# projet_pcb_nucleo_g431.net
KiCad netlist of a schematic drawn in Altium Designer
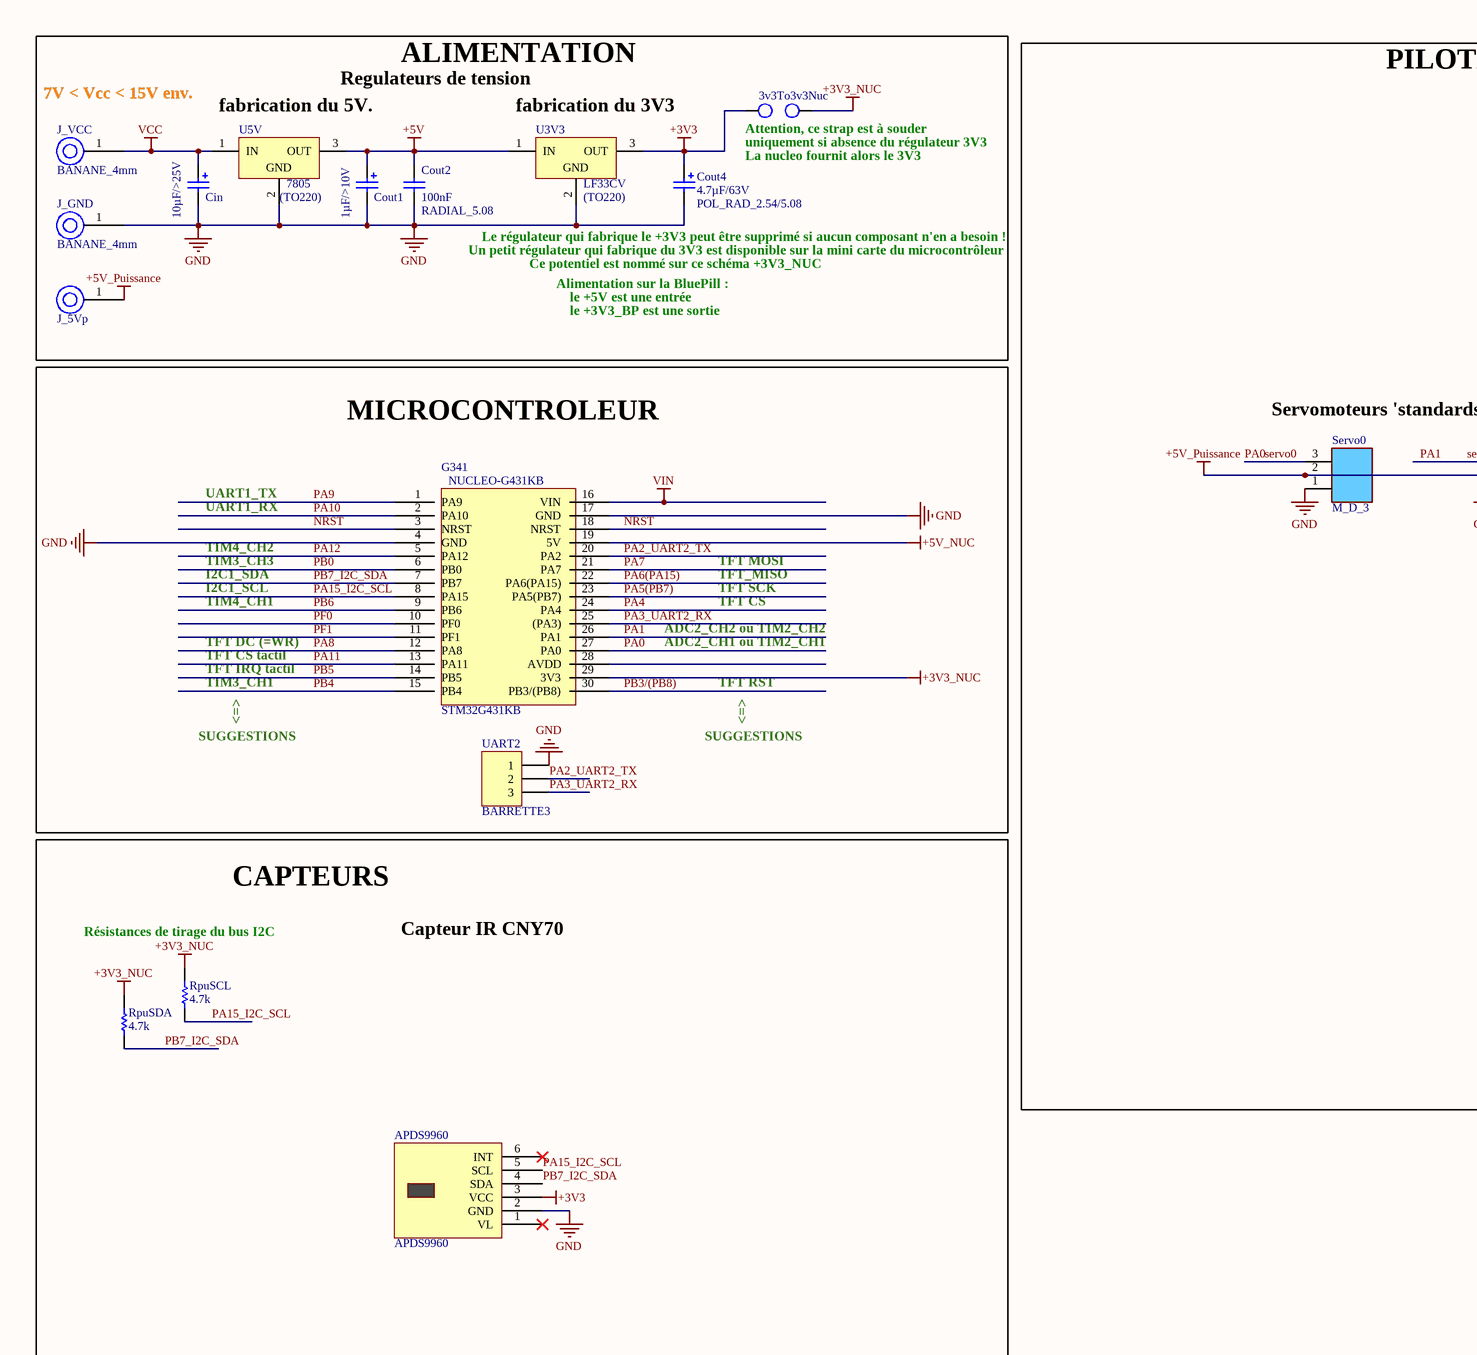
[diagram p0: projet_pcb_nucleo_g431.SchDoc, left]
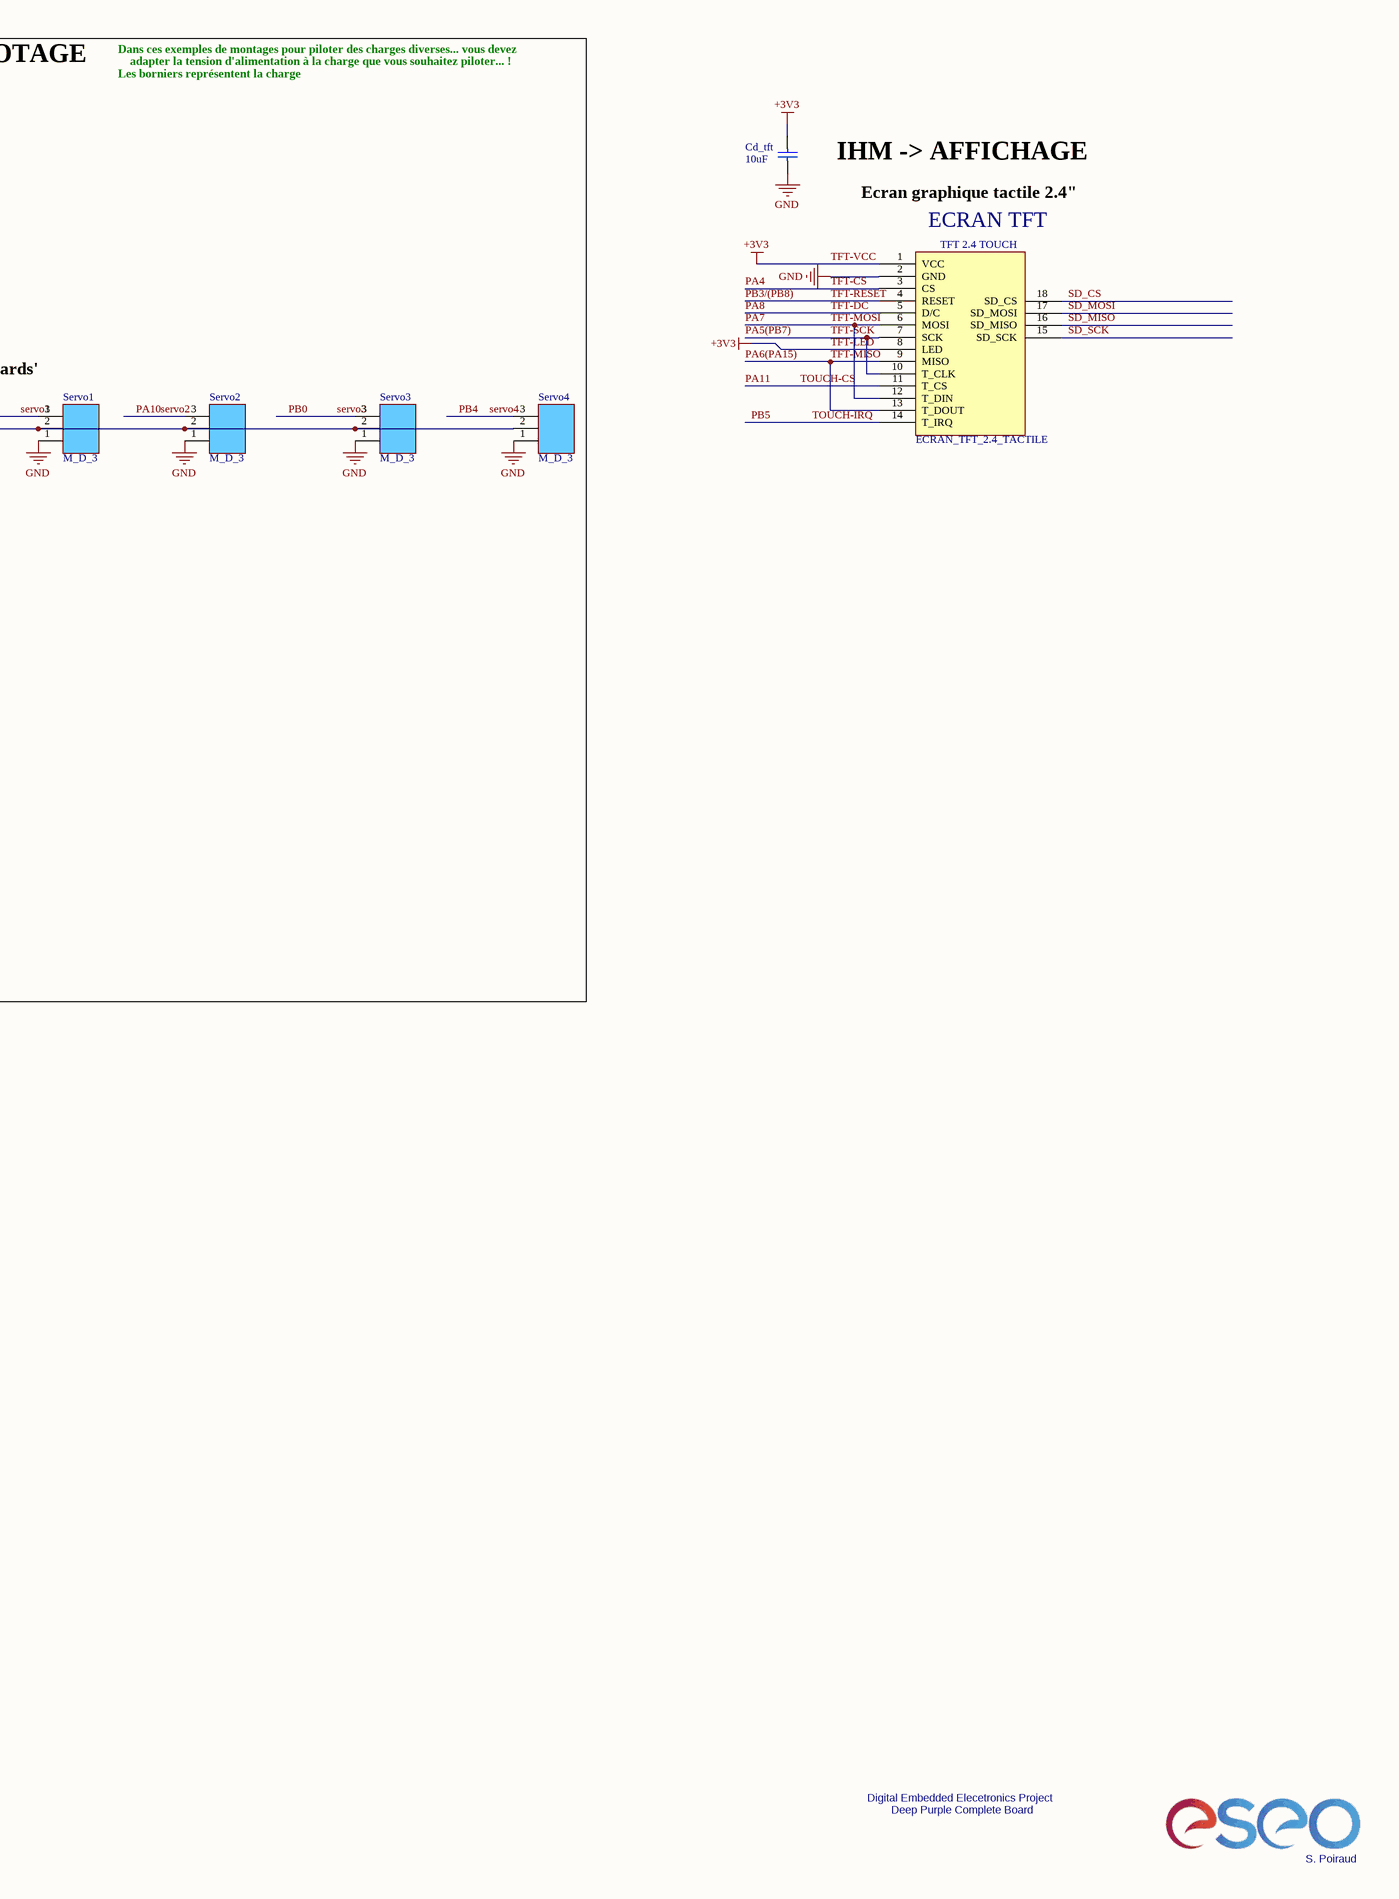
[diagram p1: projet_pcb_nucleo_g431.SchDoc, right]

(export (version "E")
  (design (tool "Eeschema 10.0.6"))
  (components
    (comp (ref "3v3To3v3Nuc")
      (value "JUMPER2")
      (footprint "BARRETTE_2_M_D")
      (description "BARRETTE 2 CONTACTS 1 RANGEE MALE DROITE")
      (libsource (lib "connecteurs") (part "JUMPER2"))
    )
    (comp (ref "APDS9960")
      (value "APDS9960")
      (footprint "APDS9960")
      (libsource (lib "DEEP") (part "APDS9960"))
    )
    (comp (ref "Cd_tft")
      (value "10uF")
      (footprint "C0805_N")
      (description "CONDENSATEUR CMS CERAMIQUE 0805")
      (libsource (lib "composants passifs") (part "CONDENSATEUR_CMS_CER_0805"))
    )
    (comp (ref "Cin")
      (value "10µF/>25V")
      (footprint "CONDENSATEUR_POLARISE_ELECTROLYTIQUE_RADIAL_2.0/5.08")
      (description "CONDENSATEUR POLARISE ELECTROLYTIQUE RADIAL 2.0/5.08")
      (fields (field (name "Comment") "CONDENSATEUR_POL_ELECTROLY_RAD_2.0/5.08"))
      (libsource (lib "composants passifs") (part "CONDENSATEUR_POL_ELECTROLY_RAD_2.0/5.08"))
    )
    (comp (ref "Cout1")
      (value "1µF/>10V")
      (footprint "CONDENSATEUR_POLARISE_ELECTROLYTIQUE_RADIAL_2.0/5.08")
      (description "CONDENSATEUR POLARISE ELECTROLYTIQUE RADIAL 2.0/5.08")
      (fields (field (name "Comment") "CONDENSATEUR_POL_ELECTROLY_RAD_2.0/5.08"))
      (libsource (lib "composants passifs") (part "CONDENSATEUR_POL_ELECTROLY_RAD_2.0/5.08"))
    )
    (comp (ref "Cout2")
      (value "100nF")
      (footprint "CONDENSATEUR_CERAMIQUE_RADIAL_5.08")
      (description "CONDENSATEUR TRAVERSANT CERAMIQUE RADIAL 5.08mm")
      (fields (field (name "TYPE") "RADIAL_5.08") (field (name "Comment") "CONDENSATEUR_CER_RAD_5.08"))
      (libsource (lib "composants passifs") (part "CONDENSATEUR_CER_RAD_5.08"))
    )
    (comp (ref "Cout4")
      (value "4.7µF/63V")
      (footprint "CONDENSATEUR_POLARISE_ELECTROLYTIQUE_RADIAL_2.54/5.08")
      (description "CONDENSATEUR POLARISE ELECTROLYTIQUE RADIAL 2.54/5.08")
      (fields
        (field (name "TYPE") "POL_RAD_2.54/5.08")
        (field (name "Comment") "CONDENSATEUR_POL_ELECTROLY_RAD_2.54/5.08")
      )
      (libsource (lib "composants passifs") (part "CONDENSATEUR_POL_ELECTROLY_RAD_2.54/5.08"))
    )
    (comp (ref "G341")
      (value "STM32G431KB")
      (footprint "NUCLEO-G431KB")
      (libsource (lib "circuits integres") (part "G431_Nucleo"))
    )
    (comp (ref "J_5Vp")
      (value "DOUILLE BANANE 4mm")
      (footprint "DOUILLE_BANANE_4mm")
      (description "DOUILLE BANANE 4 mm")
      (libsource (lib "connecteurs") (part "DOUILLE_BANANE_4mm"))
    )
    (comp (ref "J_GND")
      (value "DOUILLE BANANE 4mm")
      (footprint "DOUILLE_BANANE_4mm")
      (description "DOUILLE BANANE 4 mm")
      (fields (field (name "TYPE") "BANANE_4mm"))
      (libsource (lib "connecteurs") (part "DOUILLE_BANANE_4mm"))
    )
    (comp (ref "J_VCC")
      (value "DOUILLE BANANE 4mm")
      (footprint "DOUILLE_BANANE_4mm")
      (description "DOUILLE BANANE 4 mm")
      (fields (field (name "TYPE") "BANANE_4mm"))
      (libsource (lib "connecteurs") (part "DOUILLE_BANANE_4mm"))
    )
    (comp (ref "RpuSCL")
      (value "4.7k")
      (footprint "R1206_N")
      (description "RESISTANCE CMS 1206")
      (fields (field (name "Comment") "RESISTANCE_CMS_1206"))
      (libsource (lib "composants passifs") (part "RESISTANCE_CMS_1206"))
    )
    (comp (ref "RpuSDA")
      (value "4.7k")
      (footprint "R1206_N")
      (description "RESISTANCE CMS 1206")
      (fields (field (name "Comment") "RESISTANCE_CMS_1206"))
      (libsource (lib "composants passifs") (part "RESISTANCE_CMS_1206"))
    )
    (comp (ref "Servo0")
      (value "BARRETTE 3 CONTACTS 1 RANGEE MALE DROITE")
      (footprint "BARRETTE_3_M_D")
      (fields (field (name "TYPE") "M_D_3"))
      (libsource (lib "connecteurs") (part "BARRETTE_3 CONTACTS_1 RANGEE_MALE_DROITE"))
    )
    (comp (ref "Servo1")
      (value "BARRETTE 3 CONTACTS 1 RANGEE MALE DROITE")
      (footprint "BARRETTE_3_M_D")
      (fields (field (name "TYPE") "M_D_3"))
      (libsource (lib "connecteurs") (part "BARRETTE_3 CONTACTS_1 RANGEE_MALE_DROITE"))
    )
    (comp (ref "Servo2")
      (value "BARRETTE 3 CONTACTS 1 RANGEE MALE DROITE")
      (footprint "BARRETTE_3_M_D")
      (fields (field (name "TYPE") "M_D_3"))
      (libsource (lib "connecteurs") (part "BARRETTE_3 CONTACTS_1 RANGEE_MALE_DROITE"))
    )
    (comp (ref "Servo3")
      (value "BARRETTE 3 CONTACTS 1 RANGEE MALE DROITE")
      (footprint "BARRETTE_3_M_D")
      (fields (field (name "TYPE") "M_D_3"))
      (libsource (lib "connecteurs") (part "BARRETTE_3 CONTACTS_1 RANGEE_MALE_DROITE"))
    )
    (comp (ref "Servo4")
      (value "BARRETTE 3 CONTACTS 1 RANGEE MALE DROITE")
      (footprint "BARRETTE_3_M_D")
      (fields (field (name "TYPE") "M_D_3"))
      (libsource (lib "connecteurs") (part "BARRETTE_3 CONTACTS_1 RANGEE_MALE_DROITE"))
    )
    (comp (ref "TFT1")
      (value "ECRAN_TFT_2.4_TACTILE")
      (footprint "ECRAN_TFT_2.4_TACTILE")
      (libsource (lib "affichage") (part "ECRAN_TFT_2.4_TACTILE"))
    )
    (comp (ref "U3V3")
      (value "REGULATEUR_TO220_78XX")
      (footprint "REGULATEUR_TO220_78XX")
      (description "REGULATEUR DE TENSION POSITIVE 78XX BOITIER TO220")
      (fields (field (name "TYPE") "LF33CV") (field (name "PACKAGE") "(TO220)"))
      (libsource (lib "composants actifs") (part "REGULATEUR_TO220_78XX"))
    )
    (comp (ref "U5V")
      (value "REGULATEUR_TO220_78XX")
      (footprint "REGULATEUR_TO220_78XX")
      (description "REGULATEUR DE TENSION POSITIVE 78XX BOITIER TO220")
      (fields (field (name "TYPE") "7805") (field (name "PACKAGE") "(TO220)"))
      (libsource (lib "composants actifs") (part "REGULATEUR_TO220_78XX"))
    )
    (comp (ref "UART2")
      (value "BARRETTE3")
      (footprint "HDR1X3")
      (description "Header, 3-Pin")
      (fields (field (name "PUBLISHER") "Altium Limited"))
      (libsource (lib "Connecteur") (part "BARRETTE3"))
    )
  )
  (nets
    (net (code "1") (name "+3V3") (class "Default")
      (node (ref "3v3To3v3Nuc") (pin "1") (pinfunction "1_1") (pintype "passive"))
      (node (ref "APDS9960") (pin "3") (pinfunction "VCC_3") (pintype "passive"))
      (node (ref "Cd_tft") (pin "2") (pinfunction "2_2") (pintype "passive"))
      (node (ref "Cout4") (pin "1") (pinfunction "1_1") (pintype "passive"))
      (node (ref "TFT1") (pin "1") (pinfunction "VCC_1") (pintype "passive"))
      (node (ref "TFT1") (pin "8") (pinfunction "LED_8") (pintype "passive"))
      (node (ref "U3V3") (pin "3") (pinfunction "OUT_3") (pintype "power_in"))
    )
    (net (code "2") (name "+3V3_NUC") (class "Default")
      (node (ref "3v3To3v3Nuc") (pin "2") (pinfunction "2_2") (pintype "passive"))
      (node (ref "G341") (pin "29") (pinfunction "3V3_29") (pintype "passive"))
      (node (ref "RpuSCL") (pin "2") (pinfunction "2_2") (pintype "passive"))
      (node (ref "RpuSDA") (pin "2") (pinfunction "2_2") (pintype "passive"))
    )
    (net (code "3") (name "+5V") (class "Default")
      (node (ref "Cout1") (pin "1") (pinfunction "1_1") (pintype "passive"))
      (node (ref "Cout2") (pin "2") (pinfunction "2_2") (pintype "passive"))
      (node (ref "U3V3") (pin "1") (pinfunction "IN_1") (pintype "power_in"))
      (node (ref "U5V") (pin "3") (pinfunction "OUT_3") (pintype "power_in"))
    )
    (net (code "4") (name "+5V_NUC") (class "Default")
      (node (ref "G341") (pin "19") (pinfunction "5V_19") (pintype "power_in"))
    )
    (net (code "5") (name "+5V_Puissance") (class "Default")
      (node (ref "J_5Vp") (pin "1") (pinfunction "1_1") (pintype "passive"))
      (node (ref "Servo0") (pin "2") (pinfunction "2_2") (pintype "passive"))
      (node (ref "Servo1") (pin "2") (pinfunction "2_2") (pintype "passive"))
      (node (ref "Servo2") (pin "2") (pinfunction "2_2") (pintype "passive"))
      (node (ref "Servo3") (pin "2") (pinfunction "2_2") (pintype "passive"))
      (node (ref "Servo4") (pin "2") (pinfunction "2_2") (pintype "passive"))
    )
    (net (code "6") (name "/NRST") (class "Default")
      (node (ref "G341") (pin "18") (pinfunction "NRST_18") (pintype "passive"))
      (node (ref "G341") (pin "3") (pinfunction "NRST_3") (pintype "passive"))
    )
    (net (code "7") (name "/PA0") (class "Default")
      (node (ref "G341") (pin "27") (pinfunction "PA0_27") (pintype "passive"))
      (node (ref "Servo0") (pin "3") (pinfunction "3_3") (pintype "passive"))
    )
    (net (code "8") (name "/PA1") (class "Default")
      (node (ref "G341") (pin "26") (pinfunction "PA1_26") (pintype "passive"))
      (node (ref "Servo1") (pin "3") (pinfunction "3_3") (pintype "passive"))
    )
    (net (code "9") (name "/PA2_UART2_TX") (class "Default")
      (node (ref "G341") (pin "20") (pinfunction "PA2_20") (pintype "passive"))
      (node (ref "UART2") (pin "2") (pinfunction "2_2") (pintype "passive"))
    )
    (net (code "10") (name "/PA3_UART2_RX") (class "Default")
      (node (ref "G341") (pin "25") (pinfunction "(PA3)_25") (pintype "passive"))
      (node (ref "UART2") (pin "3") (pinfunction "3_3") (pintype "passive"))
    )
    (net (code "11") (name "/PA4") (class "Default")
      (node (ref "G341") (pin "24") (pinfunction "PA4_24") (pintype "passive"))
      (node (ref "TFT1") (pin "3") (pinfunction "CS_3") (pintype "passive"))
    )
    (net (code "12") (name "/PA5(PB7)") (class "Default")
      (node (ref "G341") (pin "23") (pinfunction "PA5(PB7)_23") (pintype "passive"))
      (node (ref "TFT1") (pin "10") (pinfunction "T_CLK_10") (pintype "passive"))
      (node (ref "TFT1") (pin "7") (pinfunction "SCK_7") (pintype "passive"))
    )
    (net (code "13") (name "/PA6(PA15)") (class "Default")
      (node (ref "G341") (pin "22") (pinfunction "PA6(PA15)_22") (pintype "passive"))
      (node (ref "TFT1") (pin "13") (pinfunction "T_DOUT_13") (pintype "passive"))
      (node (ref "TFT1") (pin "9") (pinfunction "MISO_9") (pintype "passive"))
    )
    (net (code "14") (name "/PA7") (class "Default")
      (node (ref "G341") (pin "21") (pinfunction "PA7_21") (pintype "passive"))
      (node (ref "TFT1") (pin "12") (pinfunction "T_DIN_12") (pintype "passive"))
      (node (ref "TFT1") (pin "6") (pinfunction "MOSI_6") (pintype "passive"))
    )
    (net (code "15") (name "/PA8") (class "Default")
      (node (ref "G341") (pin "12") (pinfunction "PA8_12") (pintype "passive"))
      (node (ref "TFT1") (pin "5") (pinfunction "D/C_5") (pintype "passive"))
    )
    (net (code "16") (name "/PA9") (class "Default")
      (node (ref "G341") (pin "1") (pinfunction "PA9_1") (pintype "passive"))
    )
    (net (code "17") (name "/PA10") (class "Default")
      (node (ref "G341") (pin "2") (pinfunction "PA10_2") (pintype "passive"))
      (node (ref "Servo2") (pin "3") (pinfunction "3_3") (pintype "passive"))
    )
    (net (code "18") (name "/PA11") (class "Default")
      (node (ref "G341") (pin "13") (pinfunction "PA11_13") (pintype "passive"))
      (node (ref "TFT1") (pin "11") (pinfunction "T_CS_11") (pintype "passive"))
    )
    (net (code "19") (name "/PA12") (class "Default")
      (node (ref "G341") (pin "5") (pinfunction "PA12_5") (pintype "passive"))
    )
    (net (code "20") (name "/PA15_I2C_SCL") (class "Default")
      (node (ref "APDS9960") (pin "5") (pinfunction "SCL_5") (pintype "passive"))
      (node (ref "G341") (pin "8") (pinfunction "PA15_8") (pintype "passive"))
      (node (ref "RpuSCL") (pin "1") (pinfunction "1_1") (pintype "passive"))
    )
    (net (code "21") (name "/PB0") (class "Default")
      (node (ref "G341") (pin "6") (pinfunction "PB0_6") (pintype "passive"))
      (node (ref "Servo3") (pin "3") (pinfunction "3_3") (pintype "passive"))
    )
    (net (code "22") (name "/PB3{slash}(PB8)") (class "Default")
      (node (ref "G341") (pin "30") (pinfunction "PB3/(PB8)_30") (pintype "passive"))
      (node (ref "TFT1") (pin "4") (pinfunction "RESET_4") (pintype "passive"))
    )
    (net (code "23") (name "/PB4") (class "Default")
      (node (ref "G341") (pin "15") (pinfunction "PB4_15") (pintype "passive"))
      (node (ref "Servo4") (pin "3") (pinfunction "3_3") (pintype "passive"))
    )
    (net (code "24") (name "/PB5") (class "Default")
      (node (ref "G341") (pin "14") (pinfunction "PB5_14") (pintype "passive"))
      (node (ref "TFT1") (pin "14") (pinfunction "T_IRQ_14") (pintype "passive"))
    )
    (net (code "25") (name "/PB6") (class "Default")
      (node (ref "G341") (pin "9") (pinfunction "PB6_9") (pintype "passive"))
    )
    (net (code "26") (name "/PB7_I2C_SDA") (class "Default")
      (node (ref "APDS9960") (pin "4") (pinfunction "SDA_4") (pintype "passive"))
      (node (ref "G341") (pin "7") (pinfunction "PB7_7") (pintype "passive"))
      (node (ref "RpuSDA") (pin "1") (pinfunction "1_1") (pintype "passive"))
    )
    (net (code "27") (name "/PF0") (class "Default")
      (node (ref "G341") (pin "10") (pinfunction "PF0_10") (pintype "passive"))
    )
    (net (code "28") (name "/PF1") (class "Default")
      (node (ref "G341") (pin "11") (pinfunction "PF1_11") (pintype "passive"))
    )
    (net (code "29") (name "/SD_CS") (class "Default")
      (node (ref "TFT1") (pin "18") (pinfunction "SD_CS_18") (pintype "passive"))
    )
    (net (code "30") (name "/SD_MISO") (class "Default")
      (node (ref "TFT1") (pin "16") (pinfunction "SD_MISO_16") (pintype "passive"))
    )
    (net (code "31") (name "/SD_MOSI") (class "Default")
      (node (ref "TFT1") (pin "17") (pinfunction "SD_MOSI_17") (pintype "passive"))
    )
    (net (code "32") (name "/SD_SCK") (class "Default")
      (node (ref "TFT1") (pin "15") (pinfunction "SD_SCK_15") (pintype "passive"))
    )
    (net (code "33") (name "GND") (class "Default")
      (node (ref "APDS9960") (pin "2") (pinfunction "GND_2") (pintype "passive"))
      (node (ref "Cd_tft") (pin "1") (pinfunction "1_1") (pintype "passive"))
      (node (ref "Cin") (pin "2") (pinfunction "2_2") (pintype "passive"))
      (node (ref "Cout1") (pin "2") (pinfunction "2_2") (pintype "passive"))
      (node (ref "Cout2") (pin "1") (pinfunction "1_1") (pintype "passive"))
      (node (ref "Cout4") (pin "2") (pinfunction "2_2") (pintype "passive"))
      (node (ref "G341") (pin "17") (pinfunction "GND_17") (pintype "power_in"))
      (node (ref "G341") (pin "4") (pinfunction "GND_4") (pintype "power_in"))
      (node (ref "J_GND") (pin "1") (pinfunction "1_1") (pintype "passive"))
      (node (ref "Servo0") (pin "1") (pinfunction "1_1") (pintype "passive"))
      (node (ref "Servo1") (pin "1") (pinfunction "1_1") (pintype "passive"))
      (node (ref "Servo2") (pin "1") (pinfunction "1_1") (pintype "passive"))
      (node (ref "Servo3") (pin "1") (pinfunction "1_1") (pintype "passive"))
      (node (ref "Servo4") (pin "1") (pinfunction "1_1") (pintype "passive"))
      (node (ref "TFT1") (pin "2") (pinfunction "GND_2") (pintype "passive"))
      (node (ref "U3V3") (pin "2") (pinfunction "GND_2") (pintype "power_in"))
      (node (ref "U5V") (pin "2") (pinfunction "GND_2") (pintype "power_in"))
      (node (ref "UART2") (pin "1") (pinfunction "1_1") (pintype "passive"))
    )
    (net (code "34") (name "VCC") (class "Default")
      (node (ref "Cin") (pin "1") (pinfunction "1_1") (pintype "passive"))
      (node (ref "J_VCC") (pin "1") (pinfunction "1_1") (pintype "passive"))
      (node (ref "U5V") (pin "1") (pinfunction "IN_1") (pintype "power_in"))
    )
    (net (code "35") (name "VIN") (class "Default")
      (node (ref "G341") (pin "16") (pinfunction "VIN_16") (pintype "power_in"))
    )
    (net (code "36") (name "unconnected-(APDS9960-INT-Pad6)") (class "Default")
      (node (ref "APDS9960") (pin "6") (pinfunction "INT_6") (pintype "passive+no_connect"))
    )
    (net (code "37") (name "unconnected-(APDS9960-VL-Pad1)") (class "Default")
      (node (ref "APDS9960") (pin "1") (pinfunction "VL_1") (pintype "passive+no_connect"))
    )
    (net (code "38") (name "unconnected-(G341-AVDD-Pad28)") (class "Default")
      (node (ref "G341") (pin "28") (pinfunction "AVDD_28") (pintype "passive"))
    )
  )
)
